# 8RelaySwitchOrig.net
KiCad netlist of a schematic drawn in EAGLE
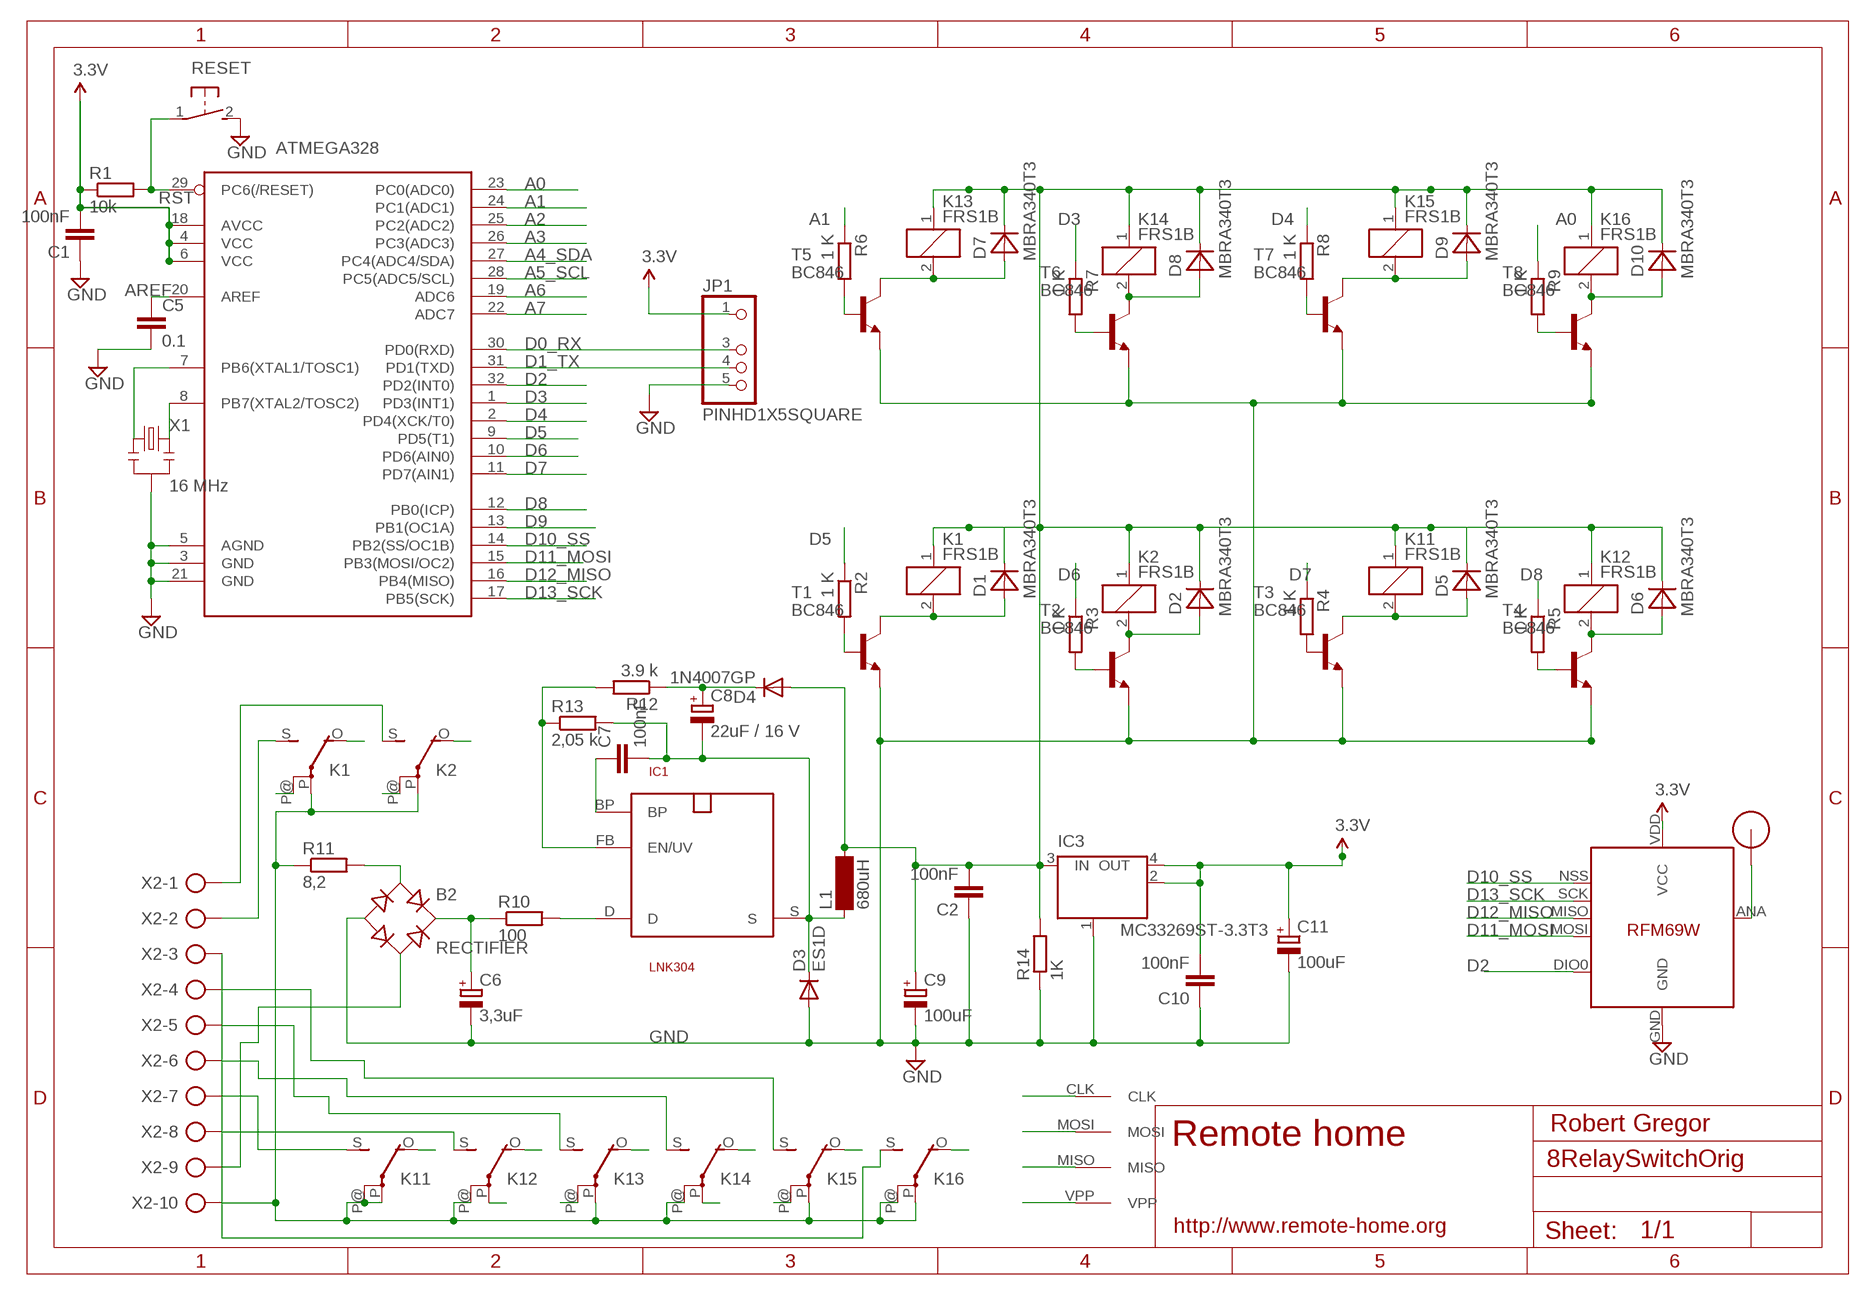
[diagram p0: schematic, sheet 1]

(export (version "E")
  (design (tool "Eeschema 10.0.6"))
  (components
    (comp (ref "ATMEGA328")
      (value "ATMega-328")
      (footprint "eagle-import:TQFP32-08")
      (libsource (lib "eagle-import") (part "ATMEGA168/328TQFP32"))
    )
    (comp (ref "B2")
      (value "RECTIFIER")
      (footprint "eagle-import:TO-269AA")
      (libsource (lib "eagle-import") (part "RECTIFIER-S40"))
    )
    (comp (ref "C1")
      (value "100nF")
      (footprint "eagle-import:C2012")
      (libsource (lib "eagle-import") (part "C-EUC2012"))
    )
    (comp (ref "C2")
      (value "100nF")
      (footprint "eagle-import:C2012")
      (libsource (lib "eagle-import") (part "C-EUC2012"))
    )
    (comp (ref "C5")
      (value "0.1")
      (footprint "eagle-import:C2012")
      (libsource (lib "eagle-import") (part "C-EUC2012"))
    )
    (comp (ref "C6")
      (value "3,3uF")
      (footprint "eagle-import:E5-10,5")
      (libsource (lib "eagle-import") (part "CPOL-EUE5-10.5"))
    )
    (comp (ref "C7")
      (value "100nF")
      (footprint "eagle-import:C2012")
      (libsource (lib "eagle-import") (part "C-EUC2012"))
    )
    (comp (ref "C8")
      (value "22uF / 16 V")
      (footprint "eagle-import:SMC_C")
      (libsource (lib "eagle-import") (part "CPOL-EUSMCC"))
    )
    (comp (ref "C9")
      (value "100uF")
      (footprint "eagle-import:SMC_B")
      (libsource (lib "eagle-import") (part "CPOL-EUSMCB"))
    )
    (comp (ref "C10")
      (value "100nF")
      (footprint "eagle-import:C2012")
      (libsource (lib "eagle-import") (part "C-EUC2012"))
    )
    (comp (ref "C11")
      (value "100uF")
      (footprint "eagle-import:SMC_B")
      (libsource (lib "eagle-import") (part "CPOL-EUSMCB"))
    )
    (comp (ref "D1")
      (value "MBRA340T3")
      (footprint "eagle-import:SMA")
      (libsource (lib "eagle-import") (part "MBRA340T3"))
    )
    (comp (ref "D2")
      (value "MBRA340T3")
      (footprint "eagle-import:SMA")
      (libsource (lib "eagle-import") (part "MBRA340T3"))
    )
    (comp (ref "D3")
      (value "ES1D")
      (footprint "eagle-import:DO214AC")
      (libsource (lib "eagle-import") (part "DIODE-DO214AC"))
    )
    (comp (ref "D4")
      (value "1N4007GP")
      (footprint "eagle-import:DO214AA")
      (libsource (lib "eagle-import") (part "DIODE-DO214AA"))
    )
    (comp (ref "D5")
      (value "MBRA340T3")
      (footprint "eagle-import:SMA")
      (libsource (lib "eagle-import") (part "MBRA340T3"))
    )
    (comp (ref "D6")
      (value "MBRA340T3")
      (footprint "eagle-import:SMA")
      (libsource (lib "eagle-import") (part "MBRA340T3"))
    )
    (comp (ref "D7")
      (value "MBRA340T3")
      (footprint "eagle-import:SMA")
      (libsource (lib "eagle-import") (part "MBRA340T3"))
    )
    (comp (ref "D8")
      (value "MBRA340T3")
      (footprint "eagle-import:SMA")
      (libsource (lib "eagle-import") (part "MBRA340T3"))
    )
    (comp (ref "D9")
      (value "MBRA340T3")
      (footprint "eagle-import:SMA")
      (libsource (lib "eagle-import") (part "MBRA340T3"))
    )
    (comp (ref "D10")
      (value "MBRA340T3")
      (footprint "eagle-import:SMA")
      (libsource (lib "eagle-import") (part "MBRA340T3"))
    )
    (comp (ref "IC1")
      (value "LNK304")
      (footprint "eagle-import:SO-8C")
      (libsource (lib "eagle-import") (part "SO-8C"))
    )
    (comp (ref "IC3")
      (value "MC33269ST-3.3T3")
      (footprint "eagle-import:SOT223")
      (libsource (lib "eagle-import") (part "MC33269ST-3.3T3"))
    )
    (comp (ref "JP1")
      (value "PINHD1X5SQUARE")
      (footprint "eagle-import:PINHD1X05-SQUARE")
      (libsource (lib "eagle-import") (part "PINHD1X5SQUARE"))
    )
    (comp (ref "K1")
      (value "FRS1B")
      (footprint "eagle-import:FRS1B")
      (libsource (lib "eagle-import") (part "FRS1B"))
    )
    (comp (ref "K2")
      (value "FRS1B")
      (footprint "eagle-import:FRS1B")
      (libsource (lib "eagle-import") (part "FRS1B"))
    )
    (comp (ref "K11")
      (value "FRS1B")
      (footprint "eagle-import:FRS1B")
      (libsource (lib "eagle-import") (part "FRS1B"))
    )
    (comp (ref "K12")
      (value "FRS1B")
      (footprint "eagle-import:FRS1B")
      (libsource (lib "eagle-import") (part "FRS1B"))
    )
    (comp (ref "K13")
      (value "FRS1B")
      (footprint "eagle-import:FRS1B")
      (libsource (lib "eagle-import") (part "FRS1B"))
    )
    (comp (ref "K14")
      (value "FRS1B")
      (footprint "eagle-import:FRS1B")
      (libsource (lib "eagle-import") (part "FRS1B"))
    )
    (comp (ref "K15")
      (value "FRS1B")
      (footprint "eagle-import:FRS1B")
      (libsource (lib "eagle-import") (part "FRS1B"))
    )
    (comp (ref "K16")
      (value "FRS1B")
      (footprint "eagle-import:FRS1B")
      (libsource (lib "eagle-import") (part "FRS1B"))
    )
    (comp (ref "L1")
      (value "680uH")
      (footprint "eagle-import:SD8")
      (libsource (lib "eagle-import") (part "SD8"))
    )
    (comp (ref "R1")
      (value "10k")
      (footprint "eagle-import:R2012")
      (libsource (lib "eagle-import") (part "R-EU_R2012"))
    )
    (comp (ref "R2")
      (value "1 K")
      (footprint "eagle-import:M2012")
      (libsource (lib "eagle-import") (part "R-EU_M2012"))
    )
    (comp (ref "R3")
      (value "1 K")
      (footprint "eagle-import:M2012")
      (libsource (lib "eagle-import") (part "R-EU_M2012"))
    )
    (comp (ref "R4")
      (value "1 K")
      (footprint "eagle-import:M2012")
      (libsource (lib "eagle-import") (part "R-EU_M2012"))
    )
    (comp (ref "R5")
      (value "1 K")
      (footprint "eagle-import:M2012")
      (libsource (lib "eagle-import") (part "R-EU_M2012"))
    )
    (comp (ref "R6")
      (value "1 K")
      (footprint "eagle-import:M2012")
      (libsource (lib "eagle-import") (part "R-EU_M2012"))
    )
    (comp (ref "R7")
      (value "1 K")
      (footprint "eagle-import:M2012")
      (libsource (lib "eagle-import") (part "R-EU_M2012"))
    )
    (comp (ref "R8")
      (value "1 K")
      (footprint "eagle-import:M2012")
      (libsource (lib "eagle-import") (part "R-EU_M2012"))
    )
    (comp (ref "R9")
      (value "1 K")
      (footprint "eagle-import:M2012")
      (libsource (lib "eagle-import") (part "R-EU_M2012"))
    )
    (comp (ref "R10")
      (value "100")
      (footprint "eagle-import:R2512W")
      (libsource (lib "eagle-import") (part "R-EU_R2512W"))
    )
    (comp (ref "R11")
      (value "8,2")
      (footprint "eagle-import:0411_12")
      (libsource (lib "eagle-import") (part "R-EU_0411/12"))
    )
    (comp (ref "R12")
      (value "3.9 k")
      (footprint "eagle-import:M2012")
      (libsource (lib "eagle-import") (part "R-EU_M2012"))
    )
    (comp (ref "R13")
      (value "2,05 k")
      (footprint "eagle-import:M2012")
      (libsource (lib "eagle-import") (part "R-EU_M2012"))
    )
    (comp (ref "R14")
      (value "1K")
      (footprint "eagle-import:M2012")
      (libsource (lib "eagle-import") (part "R-EU_M2012"))
    )
    (comp (ref "RESET")
      (value "DTSM-3")
      (footprint "eagle-import:DTSM-3")
      (libsource (lib "eagle-import") (part "DTSM-3"))
    )
    (comp (ref "T1")
      (value "BC846")
      (footprint "eagle-import:SOT23")
      (libsource (lib "eagle-import") (part "BC846"))
    )
    (comp (ref "T2")
      (value "BC846")
      (footprint "eagle-import:SOT23")
      (libsource (lib "eagle-import") (part "BC846"))
    )
    (comp (ref "T3")
      (value "BC846")
      (footprint "eagle-import:SOT23")
      (libsource (lib "eagle-import") (part "BC846"))
    )
    (comp (ref "T4")
      (value "BC846")
      (footprint "eagle-import:SOT23")
      (libsource (lib "eagle-import") (part "BC846"))
    )
    (comp (ref "T5")
      (value "BC846")
      (footprint "eagle-import:SOT23")
      (libsource (lib "eagle-import") (part "BC846"))
    )
    (comp (ref "T6")
      (value "BC846")
      (footprint "eagle-import:SOT23")
      (libsource (lib "eagle-import") (part "BC846"))
    )
    (comp (ref "T7")
      (value "BC846")
      (footprint "eagle-import:SOT23")
      (libsource (lib "eagle-import") (part "BC846"))
    )
    (comp (ref "T8")
      (value "BC846")
      (footprint "eagle-import:SOT23")
      (libsource (lib "eagle-import") (part "BC846"))
    )
    (comp (ref "U$1")
      (value "RFM12B_ANTENNA")
      (footprint "eagle-import:RFM12B-ANTENNA")
      (libsource (lib "eagle-import") (part "RFM12B_ANTENNA"))
    )
    (comp (ref "U$2")
      (value "AVRHEADERDIP")
      (footprint "eagle-import:AVRHEADER")
      (libsource (lib "eagle-import") (part "AVRHEADERDIP"))
    )
    (comp (ref "U$5")
      (value "RFM69")
      (footprint "eagle-import:RFM69W-MINPADS")
      (libsource (lib "eagle-import") (part "RFM69"))
    )
    (comp (ref "X1")
      (value "16 MHz")
      (footprint "eagle-import:RESONATOR-SMD")
      (libsource (lib "eagle-import") (part "RESONATORSMD"))
    )
    (comp (ref "X2")
      (value "AK500/10")
      (footprint "eagle-import:AK500_10")
      (libsource (lib "eagle-import") (part "AK500/10"))
    )
  )
  (nets
    (net (code "1") (name "/A0") (class "Default")
      (node (ref "ATMEGA328") (pin "23") (pinfunction "PC0(ADC0)_23") (pintype "bidirectional"))
      (node (ref "R9") (pin "1") (pinfunction "1_1") (pintype "passive"))
    )
    (net (code "2") (name "/A1") (class "Default")
      (node (ref "ATMEGA328") (pin "24") (pinfunction "PC1(ADC1)_24") (pintype "bidirectional"))
      (node (ref "R6") (pin "1") (pinfunction "1_1") (pintype "passive"))
    )
    (net (code "3") (name "/A2") (class "Default")
      (node (ref "ATMEGA328") (pin "25") (pinfunction "PC2(ADC2)_25") (pintype "bidirectional"))
    )
    (net (code "4") (name "/A3") (class "Default")
      (node (ref "ATMEGA328") (pin "26") (pinfunction "PC3(ADC3)_26") (pintype "bidirectional"))
    )
    (net (code "5") (name "/A4_SDA") (class "Default")
      (node (ref "ATMEGA328") (pin "27") (pinfunction "PC4(ADC4/SDA)_27") (pintype "bidirectional"))
    )
    (net (code "6") (name "/A5_SCL") (class "Default")
      (node (ref "ATMEGA328") (pin "28") (pinfunction "PC5(ADC5/SCL)_28") (pintype "bidirectional"))
    )
    (net (code "7") (name "/A6") (class "Default")
      (node (ref "ATMEGA328") (pin "19") (pinfunction "ADC6_19") (pintype "bidirectional"))
    )
    (net (code "8") (name "/A7") (class "Default")
      (node (ref "ATMEGA328") (pin "22") (pinfunction "ADC7_22") (pintype "bidirectional"))
    )
    (net (code "9") (name "/AREF") (class "Default")
      (node (ref "ATMEGA328") (pin "20") (pinfunction "AREF_20") (pintype "bidirectional"))
      (node (ref "C5") (pin "1") (pinfunction "1_1") (pintype "passive"))
    )
    (net (code "10") (name "/D0_RX") (class "Default")
      (node (ref "ATMEGA328") (pin "30") (pinfunction "PD0(RXD)_30") (pintype "bidirectional"))
      (node (ref "JP1") (pin "3") (pinfunction "3_3") (pintype "passive"))
    )
    (net (code "11") (name "/D1_TX") (class "Default")
      (node (ref "ATMEGA328") (pin "31") (pinfunction "PD1(TXD)_31") (pintype "bidirectional"))
      (node (ref "JP1") (pin "4") (pinfunction "4_4") (pintype "passive"))
    )
    (net (code "12") (name "/D2") (class "Default")
      (node (ref "ATMEGA328") (pin "32") (pinfunction "PD2(INT0)_32") (pintype "bidirectional"))
      (node (ref "U$5") (pin "DIO0") (pinfunction "DIO0_DIO0") (pintype "open_collector"))
    )
    (net (code "13") (name "/D3") (class "Default")
      (node (ref "ATMEGA328") (pin "1") (pinfunction "PD3(INT1)_1") (pintype "bidirectional"))
      (node (ref "R7") (pin "1") (pinfunction "1_1") (pintype "passive"))
    )
    (net (code "14") (name "/D4") (class "Default")
      (node (ref "ATMEGA328") (pin "2") (pinfunction "PD4(XCK/T0)_2") (pintype "bidirectional"))
      (node (ref "R8") (pin "1") (pinfunction "1_1") (pintype "passive"))
    )
    (net (code "15") (name "/D5") (class "Default")
      (node (ref "ATMEGA328") (pin "9") (pinfunction "PD5(T1)_9") (pintype "bidirectional"))
      (node (ref "R2") (pin "1") (pinfunction "1_1") (pintype "passive"))
    )
    (net (code "16") (name "/D6") (class "Default")
      (node (ref "ATMEGA328") (pin "10") (pinfunction "PD6(AIN0)_10") (pintype "bidirectional"))
      (node (ref "R3") (pin "1") (pinfunction "1_1") (pintype "passive"))
    )
    (net (code "17") (name "/D7") (class "Default")
      (node (ref "ATMEGA328") (pin "11") (pinfunction "PD7(AIN1)_11") (pintype "bidirectional"))
      (node (ref "R4") (pin "1") (pinfunction "1_1") (pintype "passive"))
    )
    (net (code "18") (name "/D8") (class "Default")
      (node (ref "ATMEGA328") (pin "12") (pinfunction "PB0(ICP)_12") (pintype "bidirectional"))
      (node (ref "R5") (pin "1") (pinfunction "1_1") (pintype "passive"))
    )
    (net (code "19") (name "/D9") (class "Default")
      (node (ref "ATMEGA328") (pin "13") (pinfunction "PB1(OC1A)_13") (pintype "bidirectional"))
    )
    (net (code "20") (name "/D10_SS") (class "Default")
      (node (ref "ATMEGA328") (pin "14") (pinfunction "PB2(SS/OC1B)_14") (pintype "bidirectional"))
      (node (ref "U$5") (pin "NSS") (pinfunction "SEL_NSS") (pintype "input"))
    )
    (net (code "21") (name "/D11_MOSI") (class "Default")
      (node (ref "ATMEGA328") (pin "15") (pinfunction "PB3(MOSI/OC2)_15") (pintype "bidirectional"))
      (node (ref "U$2") (pin "MOSI") (pinfunction "MOSI_MOSI") (pintype "bidirectional"))
      (node (ref "U$5") (pin "MOSI") (pinfunction "MOSI_MOSI") (pintype "output"))
    )
    (net (code "22") (name "/D12_MISO") (class "Default")
      (node (ref "ATMEGA328") (pin "16") (pinfunction "PB4(MISO)_16") (pintype "bidirectional"))
      (node (ref "U$2") (pin "MISO") (pinfunction "MISO_MISO") (pintype "bidirectional"))
      (node (ref "U$5") (pin "MISO") (pinfunction "MISO_MISO") (pintype "input"))
    )
    (net (code "23") (name "/D13_SCK") (class "Default")
      (node (ref "ATMEGA328") (pin "17") (pinfunction "PB5(SCK)_17") (pintype "bidirectional"))
      (node (ref "U$2") (pin "CLK") (pinfunction "CLK_CLK") (pintype "bidirectional"))
      (node (ref "U$5") (pin "SCK") (pinfunction "SCK_SCK") (pintype "input"))
    )
    (net (code "24") (name "/RST") (class "Default")
      (node (ref "ATMEGA328") (pin "29") (pinfunction "PC6(/RESET)_29") (pintype "bidirectional"))
      (node (ref "R1") (pin "2") (pinfunction "2_2") (pintype "passive"))
      (node (ref "RESET") (pin "1") (pinfunction "1_1") (pintype "passive"))
      (node (ref "U$2") (pin "VPP") (pinfunction "VPP_VPP") (pintype "bidirectional"))
    )
    (net (code "25") (name "3.3V") (class "Default")
      (node (ref "ATMEGA328") (pin "18") (pinfunction "AVCC_18") (pintype "bidirectional"))
      (node (ref "ATMEGA328") (pin "4") (pinfunction "VCC_4") (pintype "bidirectional"))
      (node (ref "ATMEGA328") (pin "6") (pinfunction "VCC_6") (pintype "bidirectional"))
      (node (ref "C1") (pin "2") (pinfunction "2_2") (pintype "passive"))
      (node (ref "C10") (pin "2") (pinfunction "2_2") (pintype "passive"))
      (node (ref "C11") (pin "+") (pinfunction "+_+") (pintype "passive"))
      (node (ref "IC3") (pin "2") (pinfunction "OUT_2") (pintype "passive"))
      (node (ref "IC3") (pin "4") (pinfunction "OUT_4") (pintype "passive"))
      (node (ref "JP1") (pin "1") (pinfunction "1_1") (pintype "passive"))
      (node (ref "R1") (pin "1") (pinfunction "1_1") (pintype "passive"))
      (node (ref "U$5") (pin "VDD") (pinfunction "VCC_VDD") (pintype "power_in"))
    )
    (net (code "26") (name "GND") (class "Default")
      (node (ref "ATMEGA328") (pin "21") (pinfunction "GND_21") (pintype "bidirectional"))
      (node (ref "ATMEGA328") (pin "3") (pinfunction "GND_3") (pintype "bidirectional"))
      (node (ref "ATMEGA328") (pin "5") (pinfunction "AGND_5") (pintype "bidirectional"))
      (node (ref "B2") (pin "-") (pinfunction "-_-") (pintype "passive"))
      (node (ref "C1") (pin "1") (pinfunction "1_1") (pintype "passive"))
      (node (ref "C10") (pin "1") (pinfunction "1_1") (pintype "passive"))
      (node (ref "C11") (pin "-") (pinfunction "-_-") (pintype "passive"))
      (node (ref "C2") (pin "1") (pinfunction "1_1") (pintype "passive"))
      (node (ref "C5") (pin "2") (pinfunction "2_2") (pintype "passive"))
      (node (ref "C6") (pin "-") (pinfunction "-_-") (pintype "passive"))
      (node (ref "C9") (pin "-") (pinfunction "-_-") (pintype "passive"))
      (node (ref "D3") (pin "A") (pinfunction "A_A") (pintype "passive"))
      (node (ref "IC3") (pin "1") (pinfunction "GND/ADJ_1") (pintype "input"))
      (node (ref "JP1") (pin "5") (pinfunction "5_5") (pintype "passive"))
      (node (ref "R14") (pin "1") (pinfunction "1_1") (pintype "passive"))
      (node (ref "RESET") (pin "2") (pinfunction "2_2") (pintype "passive"))
      (node (ref "T1") (pin "2") (pinfunction "E_2") (pintype "passive"))
      (node (ref "T2") (pin "2") (pinfunction "E_2") (pintype "passive"))
      (node (ref "T3") (pin "2") (pinfunction "E_2") (pintype "passive"))
      (node (ref "T4") (pin "2") (pinfunction "E_2") (pintype "passive"))
      (node (ref "T5") (pin "2") (pinfunction "E_2") (pintype "passive"))
      (node (ref "T6") (pin "2") (pinfunction "E_2") (pintype "passive"))
      (node (ref "T7") (pin "2") (pinfunction "E_2") (pintype "passive"))
      (node (ref "T8") (pin "2") (pinfunction "E_2") (pintype "passive"))
      (node (ref "U$5") (pin "GND") (pinfunction "GND_GND") (pintype "power_in"))
      (node (ref "X1") (pin "2") (pinfunction "2_2") (pintype "passive"))
    )
    (net (code "27") (name "Net-(ATMEGA328-PB6(XTAL1{slash}TOSC1))") (class "Default")
      (node (ref "ATMEGA328") (pin "7") (pinfunction "PB6(XTAL1/TOSC1)_7") (pintype "bidirectional"))
      (node (ref "X1") (pin "1") (pinfunction "1_1") (pintype "passive"))
    )
    (net (code "28") (name "Net-(ATMEGA328-PB7(XTAL2{slash}TOSC2))") (class "Default")
      (node (ref "ATMEGA328") (pin "8") (pinfunction "PB7(XTAL2/TOSC2)_8") (pintype "bidirectional"))
      (node (ref "X1") (pin "3") (pinfunction "3_3") (pintype "passive"))
    )
    (net (code "29") (name "Net-(B2-Pad+)") (class "Default")
      (node (ref "B2") (pin "+") (pinfunction "+_+") (pintype "passive"))
      (node (ref "C6") (pin "+") (pinfunction "+_+") (pintype "passive"))
      (node (ref "R10") (pin "1") (pinfunction "1_1") (pintype "passive"))
    )
    (net (code "30") (name "Net-(B2-PadAC1)") (class "Default")
      (node (ref "B2") (pin "AC1") (pinfunction "AC1_AC1") (pintype "passive"))
      (node (ref "R11") (pin "2") (pinfunction "2_2") (pintype "passive"))
    )
    (net (code "31") (name "Net-(C7-Pad1)") (class "Default")
      (node (ref "C7") (pin "1") (pinfunction "1_1") (pintype "passive"))
      (node (ref "IC1") (pin "BP") (pinfunction "BP_BP") (pintype "passive"))
    )
    (net (code "32") (name "Net-(C7-Pad2)") (class "Default")
      (node (ref "C7") (pin "2") (pinfunction "2_2") (pintype "passive"))
      (node (ref "C8") (pin "-") (pinfunction "-_-") (pintype "passive"))
      (node (ref "D3") (pin "C") (pinfunction "C_C") (pintype "passive"))
      (node (ref "IC1") (pin "S") (pinfunction "S_S") (pintype "power_in"))
      (node (ref "L1") (pin "1") (pinfunction "1_1") (pintype "passive"))
      (node (ref "R13") (pin "2") (pinfunction "2_2") (pintype "passive"))
    )
    (net (code "33") (name "Net-(C8-Pad+)") (class "Default")
      (node (ref "C8") (pin "+") (pinfunction "+_+") (pintype "passive"))
      (node (ref "D4") (pin "C") (pinfunction "C_C") (pintype "passive"))
      (node (ref "R12") (pin "1") (pinfunction "1_1") (pintype "passive"))
    )
    (net (code "34") (name "Net-(IC1-EN{slash}UV)") (class "Default")
      (node (ref "IC1") (pin "FB") (pinfunction "EN/UV_FB") (pintype "input"))
      (node (ref "R12") (pin "2") (pinfunction "2_2") (pintype "passive"))
      (node (ref "R13") (pin "1") (pinfunction "1_1") (pintype "passive"))
    )
    (net (code "35") (name "Net-(IC1-PadD)") (class "Default")
      (node (ref "IC1") (pin "D") (pinfunction "D_D") (pintype "open_collector"))
      (node (ref "R10") (pin "2") (pinfunction "2_2") (pintype "passive"))
    )
    (net (code "36") (name "Net-(IC3-IN)") (class "Default")
      (node (ref "C2") (pin "2") (pinfunction "2_2") (pintype "passive"))
      (node (ref "C9") (pin "+") (pinfunction "+_+") (pintype "passive"))
      (node (ref "D1") (pin "C") (pinfunction "C_C") (pintype "passive"))
      (node (ref "D10") (pin "C") (pinfunction "C_C") (pintype "passive"))
      (node (ref "D2") (pin "C") (pinfunction "C_C") (pintype "passive"))
      (node (ref "D4") (pin "A") (pinfunction "A_A") (pintype "passive"))
      (node (ref "D5") (pin "C") (pinfunction "C_C") (pintype "passive"))
      (node (ref "D6") (pin "C") (pinfunction "C_C") (pintype "passive"))
      (node (ref "D7") (pin "C") (pinfunction "C_C") (pintype "passive"))
      (node (ref "D8") (pin "C") (pinfunction "C_C") (pintype "passive"))
      (node (ref "D9") (pin "C") (pinfunction "C_C") (pintype "passive"))
      (node (ref "IC3") (pin "3") (pinfunction "IN_3") (pintype "input"))
      (node (ref "K1") (pin "1") (pinfunction "1_1") (pintype "passive"))
      (node (ref "K11") (pin "1") (pinfunction "1_1") (pintype "passive"))
      (node (ref "K12") (pin "1") (pinfunction "1_1") (pintype "passive"))
      (node (ref "K13") (pin "1") (pinfunction "1_1") (pintype "passive"))
      (node (ref "K14") (pin "1") (pinfunction "1_1") (pintype "passive"))
      (node (ref "K15") (pin "1") (pinfunction "1_1") (pintype "passive"))
      (node (ref "K16") (pin "1") (pinfunction "1_1") (pintype "passive"))
      (node (ref "K2") (pin "1") (pinfunction "1_1") (pintype "passive"))
      (node (ref "L1") (pin "2") (pinfunction "2_2") (pintype "passive"))
      (node (ref "R14") (pin "2") (pinfunction "2_2") (pintype "passive"))
    )
    (net (code "37") (name "Net-(T1-B)") (class "Default")
      (node (ref "R2") (pin "2") (pinfunction "2_2") (pintype "passive"))
      (node (ref "T1") (pin "1") (pinfunction "B_1") (pintype "passive"))
    )
    (net (code "38") (name "Net-(T1-C)") (class "Default")
      (node (ref "D1") (pin "A") (pinfunction "A_A") (pintype "passive"))
      (node (ref "K1") (pin "2") (pinfunction "2_2") (pintype "passive"))
      (node (ref "T1") (pin "3") (pinfunction "C_3") (pintype "passive"))
    )
    (net (code "39") (name "Net-(T2-B)") (class "Default")
      (node (ref "R3") (pin "2") (pinfunction "2_2") (pintype "passive"))
      (node (ref "T2") (pin "1") (pinfunction "B_1") (pintype "passive"))
    )
    (net (code "40") (name "Net-(T2-C)") (class "Default")
      (node (ref "D2") (pin "A") (pinfunction "A_A") (pintype "passive"))
      (node (ref "K2") (pin "2") (pinfunction "2_2") (pintype "passive"))
      (node (ref "T2") (pin "3") (pinfunction "C_3") (pintype "passive"))
    )
    (net (code "41") (name "Net-(T3-B)") (class "Default")
      (node (ref "R4") (pin "2") (pinfunction "2_2") (pintype "passive"))
      (node (ref "T3") (pin "1") (pinfunction "B_1") (pintype "passive"))
    )
    (net (code "42") (name "Net-(T3-C)") (class "Default")
      (node (ref "D5") (pin "A") (pinfunction "A_A") (pintype "passive"))
      (node (ref "K11") (pin "2") (pinfunction "2_2") (pintype "passive"))
      (node (ref "T3") (pin "3") (pinfunction "C_3") (pintype "passive"))
    )
    (net (code "43") (name "Net-(T4-B)") (class "Default")
      (node (ref "R5") (pin "2") (pinfunction "2_2") (pintype "passive"))
      (node (ref "T4") (pin "1") (pinfunction "B_1") (pintype "passive"))
    )
    (net (code "44") (name "Net-(T4-C)") (class "Default")
      (node (ref "D6") (pin "A") (pinfunction "A_A") (pintype "passive"))
      (node (ref "K12") (pin "2") (pinfunction "2_2") (pintype "passive"))
      (node (ref "T4") (pin "3") (pinfunction "C_3") (pintype "passive"))
    )
    (net (code "45") (name "Net-(T5-B)") (class "Default")
      (node (ref "R6") (pin "2") (pinfunction "2_2") (pintype "passive"))
      (node (ref "T5") (pin "1") (pinfunction "B_1") (pintype "passive"))
    )
    (net (code "46") (name "Net-(T5-C)") (class "Default")
      (node (ref "D7") (pin "A") (pinfunction "A_A") (pintype "passive"))
      (node (ref "K13") (pin "2") (pinfunction "2_2") (pintype "passive"))
      (node (ref "T5") (pin "3") (pinfunction "C_3") (pintype "passive"))
    )
    (net (code "47") (name "Net-(T6-B)") (class "Default")
      (node (ref "R7") (pin "2") (pinfunction "2_2") (pintype "passive"))
      (node (ref "T6") (pin "1") (pinfunction "B_1") (pintype "passive"))
    )
    (net (code "48") (name "Net-(T6-C)") (class "Default")
      (node (ref "D8") (pin "A") (pinfunction "A_A") (pintype "passive"))
      (node (ref "K14") (pin "2") (pinfunction "2_2") (pintype "passive"))
      (node (ref "T6") (pin "3") (pinfunction "C_3") (pintype "passive"))
    )
    (net (code "49") (name "Net-(T7-B)") (class "Default")
      (node (ref "R8") (pin "2") (pinfunction "2_2") (pintype "passive"))
      (node (ref "T7") (pin "1") (pinfunction "B_1") (pintype "passive"))
    )
    (net (code "50") (name "Net-(T7-C)") (class "Default")
      (node (ref "D9") (pin "A") (pinfunction "A_A") (pintype "passive"))
      (node (ref "K15") (pin "2") (pinfunction "2_2") (pintype "passive"))
      (node (ref "T7") (pin "3") (pinfunction "C_3") (pintype "passive"))
    )
    (net (code "51") (name "Net-(T8-B)") (class "Default")
      (node (ref "R9") (pin "2") (pinfunction "2_2") (pintype "passive"))
      (node (ref "T8") (pin "1") (pinfunction "B_1") (pintype "passive"))
    )
    (net (code "52") (name "Net-(T8-C)") (class "Default")
      (node (ref "D10") (pin "A") (pinfunction "A_A") (pintype "passive"))
      (node (ref "K16") (pin "2") (pinfunction "2_2") (pintype "passive"))
      (node (ref "T8") (pin "3") (pinfunction "C_3") (pintype "passive"))
    )
    (net (code "53") (name "Net-(U$1-1)") (class "Default")
      (node (ref "U$1") (pin "P$1") (pinfunction "1_P$1") (pintype "bidirectional"))
      (node (ref "U$5") (pin "ANA") (pinfunction "ANT_ANA") (pintype "passive"))
    )
    (net (code "54") (name "Net-(X2A-KL)") (class "Default")
      (node (ref "K2") (pin "S") (pinfunction "S_S") (pintype "passive"))
      (node (ref "X2") (pin "1") (pinfunction "KL_1") (pintype "passive"))
    )
    (net (code "55") (name "Net-(X2B-KL)") (class "Default")
      (node (ref "K1") (pin "P") (pinfunction "P_P") (pintype "passive"))
      (node (ref "K11") (pin "P") (pinfunction "P_P") (pintype "passive"))
      (node (ref "K11") (pin "P@") (pinfunction "P_P@") (pintype "passive"))
      (node (ref "K12") (pin "P@") (pinfunction "P_P@") (pintype "passive"))
      (node (ref "K13") (pin "P") (pinfunction "P_P") (pintype "passive"))
      (node (ref "K14") (pin "P@") (pinfunction "P_P@") (pintype "passive"))
      (node (ref "K15") (pin "P") (pinfunction "P_P") (pintype "passive"))
      (node (ref "K16") (pin "P") (pinfunction "P_P") (pintype "passive"))
      (node (ref "K16") (pin "P@") (pinfunction "P_P@") (pintype "passive"))
      (node (ref "K2") (pin "P") (pinfunction "P_P") (pintype "passive"))
      (node (ref "R11") (pin "1") (pinfunction "1_1") (pintype "passive"))
      (node (ref "X2") (pin "10") (pinfunction "KL_10") (pintype "passive"))
    )
    (net (code "56") (name "Net-(X2C-KL)") (class "Default")
      (node (ref "K1") (pin "S") (pinfunction "S_S") (pintype "passive"))
      (node (ref "X2") (pin "2") (pinfunction "KL_2") (pintype "passive"))
    )
    (net (code "57") (name "Net-(X2D-KL)") (class "Default")
      (node (ref "K16") (pin "S") (pinfunction "S_S") (pintype "passive"))
      (node (ref "X2") (pin "3") (pinfunction "KL_3") (pintype "passive"))
    )
    (net (code "58") (name "Net-(X2E-KL)") (class "Default")
      (node (ref "K15") (pin "S") (pinfunction "S_S") (pintype "passive"))
      (node (ref "X2") (pin "4") (pinfunction "KL_4") (pintype "passive"))
    )
    (net (code "59") (name "Net-(X2F-KL)") (class "Default")
      (node (ref "K13") (pin "S") (pinfunction "S_S") (pintype "passive"))
      (node (ref "X2") (pin "5") (pinfunction "KL_5") (pintype "passive"))
    )
    (net (code "60") (name "Net-(X2G-KL)") (class "Default")
      (node (ref "K14") (pin "S") (pinfunction "S_S") (pintype "passive"))
      (node (ref "X2") (pin "6") (pinfunction "KL_6") (pintype "passive"))
    )
    (net (code "61") (name "Net-(X2H-KL)") (class "Default")
      (node (ref "K11") (pin "S") (pinfunction "S_S") (pintype "passive"))
      (node (ref "X2") (pin "7") (pinfunction "KL_7") (pintype "passive"))
    )
    (net (code "62") (name "Net-(X2I-KL)") (class "Default")
      (node (ref "K12") (pin "S") (pinfunction "S_S") (pintype "passive"))
      (node (ref "X2") (pin "8") (pinfunction "KL_8") (pintype "passive"))
    )
    (net (code "63") (name "Net-(X2J-KL)") (class "Default")
      (node (ref "B2") (pin "AC2") (pinfunction "AC2_AC2") (pintype "passive"))
      (node (ref "X2") (pin "9") (pinfunction "KL_9") (pintype "passive"))
    )
    (net (code "64") (name "unconnected-(K1-PadO)") (class "Default")
      (node (ref "K1") (pin "O") (pinfunction "O_O") (pintype "passive"))
    )
    (net (code "65") (name "unconnected-(K1B-P-PadP@)") (class "Default")
      (node (ref "K1") (pin "P@") (pinfunction "P_P@") (pintype "passive"))
    )
    (net (code "66") (name "unconnected-(K2-PadO)") (class "Default")
      (node (ref "K2") (pin "O") (pinfunction "O_O") (pintype "passive"))
    )
    (net (code "67") (name "unconnected-(K2B-P-PadP@)") (class "Default")
      (node (ref "K2") (pin "P@") (pinfunction "P_P@") (pintype "passive"))
    )
    (net (code "68") (name "unconnected-(K11-PadO)") (class "Default")
      (node (ref "K11") (pin "O") (pinfunction "O_O") (pintype "passive"))
    )
    (net (code "69") (name "unconnected-(K12-PadO)") (class "Default")
      (node (ref "K12") (pin "O") (pinfunction "O_O") (pintype "passive"))
    )
    (net (code "70") (name "unconnected-(K12-PadP)") (class "Default")
      (node (ref "K12") (pin "P") (pinfunction "P_P") (pintype "passive"))
    )
    (net (code "71") (name "unconnected-(K13-PadO)") (class "Default")
      (node (ref "K13") (pin "O") (pinfunction "O_O") (pintype "passive"))
    )
    (net (code "72") (name "unconnected-(K13B-P-PadP@)") (class "Default")
      (node (ref "K13") (pin "P@") (pinfunction "P_P@") (pintype "passive"))
    )
    (net (code "73") (name "unconnected-(K14-PadO)") (class "Default")
      (node (ref "K14") (pin "O") (pinfunction "O_O") (pintype "passive"))
    )
    (net (code "74") (name "unconnected-(K14-PadP)") (class "Default")
      (node (ref "K14") (pin "P") (pinfunction "P_P") (pintype "passive"))
    )
    (net (code "75") (name "unconnected-(K15-PadO)") (class "Default")
      (node (ref "K15") (pin "O") (pinfunction "O_O") (pintype "passive"))
    )
    (net (code "76") (name "unconnected-(K15B-P-PadP@)") (class "Default")
      (node (ref "K15") (pin "P@") (pinfunction "P_P@") (pintype "passive"))
    )
    (net (code "77") (name "unconnected-(K16-PadO)") (class "Default")
      (node (ref "K16") (pin "O") (pinfunction "O_O") (pintype "passive"))
    )
  )
)
